# DMGC-HDP-01_2-1.net
KiCad netlist of a schematic drawn in EAGLE
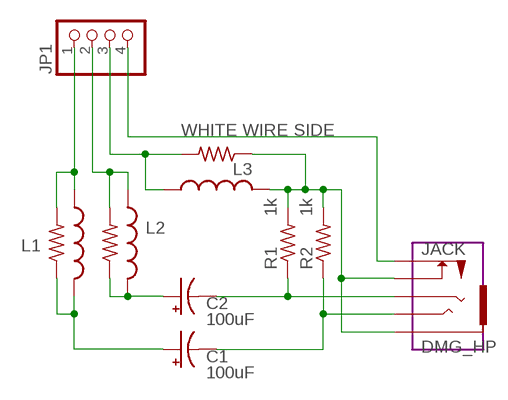
[diagram p0: schematic, sheet 1]

(export (version "E")
  (design (tool "Eeschema 10.0.6"))
  (components
    (comp (ref "C1")
      (value "100uF")
      (footprint "eagle-import:E2,5-5")
      (libsource (lib "eagle-import") (part "CPOL-USE2.5-5"))
    )
    (comp (ref "C2")
      (value "100uF")
      (footprint "eagle-import:E2,5-5")
      (libsource (lib "eagle-import") (part "CPOL-USE2.5-5"))
    )
    (comp (ref "EM1")
      (value "BLM21P221SG")
      (footprint "eagle-import:R0603")
      (libsource (lib "eagle-import") (part "R-US_R0603"))
    )
    (comp (ref "EM2")
      (value "BLM21P221SG")
      (footprint "eagle-import:R0603")
      (libsource (lib "eagle-import") (part "R-US_R0603"))
    )
    (comp (ref "EM9")
      (value "BLM21P221SG")
      (footprint "eagle-import:R0603")
      (libsource (lib "eagle-import") (part "R-US_R0603"))
    )
    (comp (ref "JACK")
      (value "DMG_HP")
      (footprint "eagle-import:DMG_HP")
      (libsource (lib "eagle-import") (part "DMG_HP"))
    )
    (comp (ref "JP1")
      (value "PINHD-1X4")
      (footprint "eagle-import:1X04")
      (libsource (lib "eagle-import") (part "PINHD-1X4"))
    )
    (comp (ref "L1")
      (value "33µH")
      (footprint "eagle-import:0204_7")
      (libsource (lib "eagle-import") (part "L-US0204/7"))
    )
    (comp (ref "L2")
      (value "33µH")
      (footprint "eagle-import:0204_7")
      (libsource (lib "eagle-import") (part "L-US0204/7"))
    )
    (comp (ref "L3")
      (value "33µH")
      (footprint "eagle-import:0204_7")
      (libsource (lib "eagle-import") (part "L-US0204/7"))
    )
    (comp (ref "R1")
      (value "1k")
      (footprint "eagle-import:R0603")
      (libsource (lib "eagle-import") (part "rcl_334_R-US_R0603"))
    )
    (comp (ref "R2")
      (value "1k")
      (footprint "eagle-import:R0603")
      (libsource (lib "eagle-import") (part "rcl_334_R-US_R0603"))
    )
  )
  (nets
    (net (code "1") (name "Net-(C1-Pad+)") (class "Default")
      (node (ref "C1") (pin "+") (pinfunction "+_+") (pintype "passive"))
      (node (ref "EM9") (pin "1") (pinfunction "1_1") (pintype "passive"))
      (node (ref "L1") (pin "2") (pinfunction "2_2") (pintype "passive"))
    )
    (net (code "2") (name "Net-(C1-Pad-)") (class "Default")
      (node (ref "C1") (pin "-") (pinfunction "-_-") (pintype "passive"))
      (node (ref "JACK") (pin "T") (pinfunction "T_T") (pintype "bidirectional"))
      (node (ref "R2") (pin "1") (pinfunction "1_1") (pintype "passive"))
    )
    (net (code "3") (name "Net-(C2-Pad+)") (class "Default")
      (node (ref "C2") (pin "+") (pinfunction "+_+") (pintype "passive"))
      (node (ref "EM1") (pin "1") (pinfunction "1_1") (pintype "passive"))
      (node (ref "L2") (pin "2") (pinfunction "2_2") (pintype "passive"))
    )
    (net (code "4") (name "Net-(C2-Pad-)") (class "Default")
      (node (ref "C2") (pin "-") (pinfunction "-_-") (pintype "passive"))
      (node (ref "JACK") (pin "R") (pinfunction "R_R") (pintype "bidirectional"))
      (node (ref "R1") (pin "1") (pinfunction "1_1") (pintype "passive"))
    )
    (net (code "5") (name "Net-(EM1-Pad2)") (class "Default")
      (node (ref "EM1") (pin "2") (pinfunction "2_2") (pintype "passive"))
      (node (ref "JP1") (pin "2") (pinfunction "2_2") (pintype "passive"))
      (node (ref "L2") (pin "1") (pinfunction "1_1") (pintype "passive"))
    )
    (net (code "6") (name "Net-(EM2-Pad2)") (class "Default")
      (node (ref "EM2") (pin "2") (pinfunction "2_2") (pintype "passive"))
      (node (ref "JP1") (pin "3") (pinfunction "3_3") (pintype "passive"))
      (node (ref "L3") (pin "1") (pinfunction "1_1") (pintype "passive"))
    )
    (net (code "7") (name "Net-(EM9-Pad2)") (class "Default")
      (node (ref "EM9") (pin "2") (pinfunction "2_2") (pintype "passive"))
      (node (ref "JP1") (pin "1") (pinfunction "1_1") (pintype "passive"))
      (node (ref "L1") (pin "1") (pinfunction "1_1") (pintype "passive"))
    )
    (net (code "8") (name "Net-(JACK-S)") (class "Default")
      (node (ref "EM2") (pin "1") (pinfunction "1_1") (pintype "passive"))
      (node (ref "JACK") (pin "GND") (pinfunction "S_GND") (pintype "bidirectional"))
      (node (ref "JACK") (pin "SWGND") (pinfunction "SWB_SWGND") (pintype "bidirectional"))
      (node (ref "L3") (pin "2") (pinfunction "2_2") (pintype "passive"))
      (node (ref "R1") (pin "2") (pinfunction "2_2") (pintype "passive"))
      (node (ref "R2") (pin "2") (pinfunction "2_2") (pintype "passive"))
    )
    (net (code "9") (name "Net-(JACK-SWA)") (class "Default")
      (node (ref "JACK") (pin "SW") (pinfunction "SWA_SW") (pintype "bidirectional"))
      (node (ref "JP1") (pin "4") (pinfunction "4_4") (pintype "passive"))
    )
  )
)
